# FTDI.net
KiCad netlist of a schematic drawn in Altium Designer
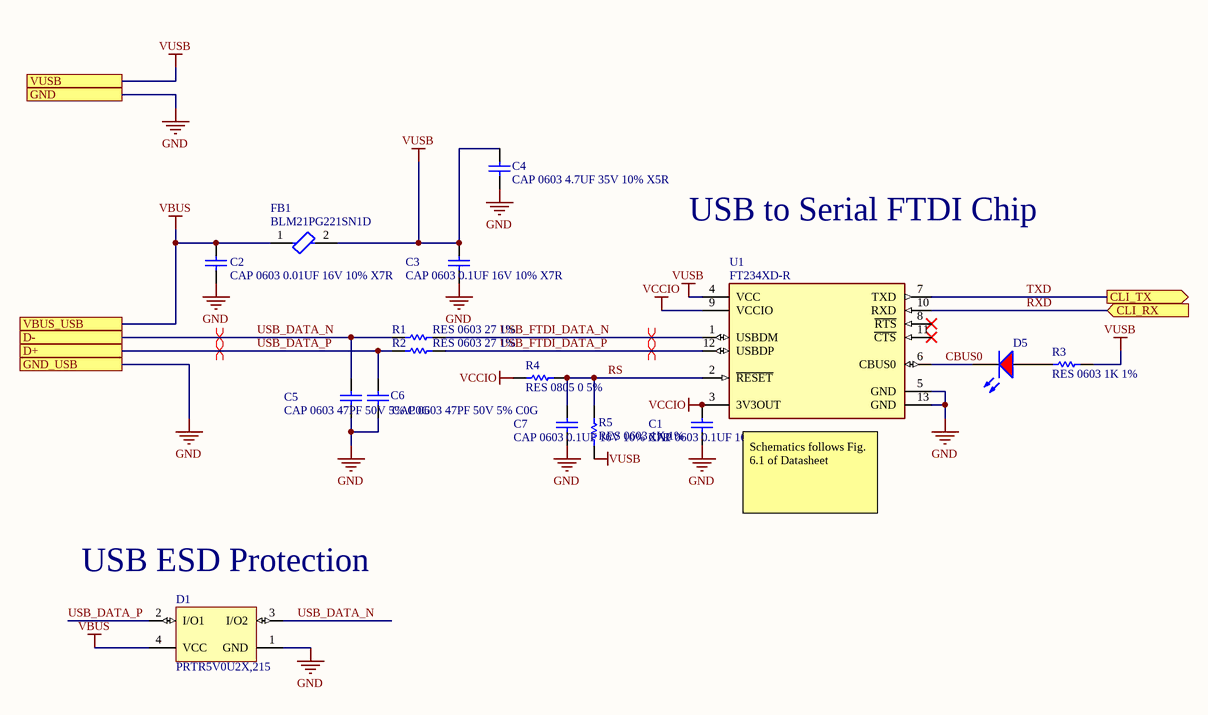
[diagram p0: FTDI.SchDoc]

(export (version "E")
  (design (tool "Eeschema 10.0.6"))
  (components
    (comp (ref "C1")
      (value "CAP 0603 0.1UF 16V 10% X7R")
      (footprint "0603_CAP")
      (description "Capacitor Surface Mount 0603 Footprint 0.1UF 16V 10% Tolerance Ceramic X7R")
      (fields (field (name "VOLTAGE") "16V") (field (name "MANUFACTURER") "Various"))
      (libsource (lib "University of Pennsylvania (ESE Labs)") (part "cap"))
    )
    (comp (ref "C2")
      (value "CAP 0603 0.01UF 16V 10% X7R")
      (footprint "0603_CAP")
      (description "Capacitor Surface Mount 0603 Footprint 0.01UF 16V 10% Tolerance Ceramic X7R")
      (fields (field (name "MANUFACTURER") "Various") (field (name "VOLTAGE") "16V"))
      (libsource (lib "University of Pennsylvania (ESE Labs)") (part "cap"))
    )
    (comp (ref "C3")
      (value "CAP 0603 0.1UF 16V 10% X7R")
      (footprint "0603_CAP")
      (description "Capacitor Surface Mount 0603 Footprint 0.1UF 16V 10% Tolerance Ceramic X7R")
      (fields (field (name "VOLTAGE") "16V") (field (name "MANUFACTURER") "Various"))
      (libsource (lib "University of Pennsylvania (ESE Labs)") (part "cap"))
    )
    (comp (ref "C4")
      (value "CAP 0603 4.7UF 35V 10% X5R")
      (footprint "0603_CAP")
      (description "Capacitor Surface Mount 0603 Footprint 47UF 35V 10% Tolerance Ceramic X5R")
      (fields (field (name "MANUFACTURER") "Various"))
      (libsource (lib "University of Pennsylvania (ESE Labs)") (part "cap"))
    )
    (comp (ref "C5")
      (value "CAP 0603 47PF 50V 5% C0G")
      (footprint "0603_CAP")
      (description "Capacitor Surface Mount 0603 Footprint 47PF 50V 5% Tolerance Ceramic C0G")
      (fields (field (name "MANUFACTURER") "Various") (field (name "VOLTAGE") "50V"))
      (libsource (lib "University of Pennsylvania (ESE Labs)") (part "cap"))
    )
    (comp (ref "C6")
      (value "CAP 0603 47PF 50V 5% C0G")
      (footprint "0603_CAP")
      (description "Capacitor Surface Mount 0603 Footprint 47PF 50V 5% Tolerance Ceramic C0G")
      (fields (field (name "MANUFACTURER") "Various") (field (name "VOLTAGE") "50V"))
      (libsource (lib "University of Pennsylvania (ESE Labs)") (part "cap"))
    )
    (comp (ref "C7")
      (value "CAP 0603 0.1UF 16V 10% X7R")
      (footprint "0603_CAP")
      (description "Capacitor Surface Mount 0603 Footprint 0.1UF 16V 10% Tolerance Ceramic X7R")
      (fields (field (name "VOLTAGE") "16V") (field (name "MANUFACTURER") "Various"))
      (libsource (lib "University of Pennsylvania (ESE Labs)") (part "cap"))
    )
    (comp (ref "D1")
      (value "PRTR5V0U2X,215")
      (footprint "NXP-SOT143B-4_V")
      (fields (field (name "MANUFACTURER") "NXP Semiconductors"))
      (libsource (lib "Altium Content Vault") (part "NXP-PRTR5V0U2X,215-4"))
    )
    (comp (ref "D5")
      (value "LSM0805412V")
      (footprint "LED_0805_RED")
      (description "Single Color LED, RED, 0805")
      (libsource (lib "University of Pennsylvania (ESE Labs)") (part "LED-RED-AK-2"))
    )
    (comp (ref "FB1")
      (value "BLM21PG221SN1D")
      (footprint "FP-BLM21-0_2-t0_85-e0_5-IPC_B")
      (description "Chip Ferrite Bead, 0805, 220Ω @ 100MHz, 0.045Ω, 25%, 2A")
      (fields (field (name "TOLERANCE") "25%"))
      (libsource (lib "Altium Content Vault") (part "5f30dd21d616792df468990f7003faa"))
    )
    (comp (ref "R1")
      (value "RES 0603 27 1%")
      (footprint "0603_RES")
      (description "Resistor Surface Mount, 27 Ohms, 0603 Footprint, 1% Tolerance 0.1W")
      (fields (field (name "TOLERANCE") "1%") (field (name "MANUFACTURER") "Various"))
      (libsource (lib "University of Pennsylvania (ESE Labs)") (part "res"))
    )
    (comp (ref "R2")
      (value "RES 0603 27 1%")
      (footprint "0603_RES")
      (description "Resistor Surface Mount, 27 Ohms, 0603 Footprint, 1% Tolerance 0.1W")
      (fields (field (name "TOLERANCE") "1%") (field (name "MANUFACTURER") "Various"))
      (libsource (lib "University of Pennsylvania (ESE Labs)") (part "res"))
    )
    (comp (ref "R3")
      (value "RES 0603 1K 1%")
      (footprint "0603_RES")
      (description "Resistor Surface Mount, 1K Ohms, 0603 Footprint, 1% Tolerance 0.1W")
      (fields (field (name "MANUFACTURER") "Various") (field (name "TOLERANCE") "1%"))
      (libsource (lib "University of Pennsylvania (ESE Labs)") (part "res"))
    )
    (comp (ref "R4")
      (value "RES 0805 0 5%")
      (footprint "0805_RES")
      (description "Resistor Surface Mount, 0 Ohms, 0805 Footprint, 5% Tolerance 0.125W")
      (fields (field (name "MANUFACTURER") "Various") (field (name "TOLERANCE") "5%"))
      (libsource (lib "University of Pennsylvania (ESE Labs)") (part "res"))
    )
    (comp (ref "R5")
      (value "RES 0603 1K 1%")
      (footprint "0603_RES")
      (description "Resistor Surface Mount, 1K Ohms, 0603 Footprint, 1% Tolerance 0.1W")
      (fields (field (name "MANUFACTURER") "Various") (field (name "TOLERANCE") "1%"))
      (libsource (lib "University of Pennsylvania (ESE Labs)") (part "res"))
    )
    (comp (ref "U1")
      (value "FT234XD-R")
      (footprint "FP-DFN-12-IPC_B")
      (description "IC USB SERIAL BASIC UART 12DFN")
      (libsource (lib "Altium Content Vault") (part "4bef3367ed9f9051bcb84ab46edda1c"))
    )
  )
  (nets
    (net (code "1") (name "/CBUS0") (class "Default")
      (node (ref "D5") (pin "K") (pinfunction "K_K") (pintype "passive"))
      (node (ref "U1") (pin "6") (pinfunction "CBUS0_6") (pintype "bidirectional"))
    )
    (net (code "2") (name "/RS") (class "Default")
      (node (ref "C7") (pin "2") (pinfunction "2_2") (pintype "passive"))
      (node (ref "R4") (pin "2") (pinfunction "2_2") (pintype "passive"))
      (node (ref "R5") (pin "2") (pinfunction "2_2") (pintype "passive"))
      (node (ref "U1") (pin "2") (pinfunction "~{RESET}_2") (pintype "input"))
    )
    (net (code "3") (name "/RXD") (class "Default")
      (node (ref "U1") (pin "10") (pinfunction "RXD_10") (pintype "input"))
    )
    (net (code "4") (name "/TXD") (class "Default")
      (node (ref "U1") (pin "7") (pinfunction "TXD_7") (pintype "output"))
    )
    (net (code "5") (name "/USB_DATA_N") (class "Default")
      (node (ref "C5") (pin "2") (pinfunction "2_2") (pintype "passive"))
      (node (ref "D1") (pin "3") (pinfunction "I/O2_3") (pintype "bidirectional"))
      (node (ref "R1") (pin "1") (pinfunction "1_1") (pintype "passive"))
    )
    (net (code "6") (name "/USB_DATA_P") (class "Default")
      (node (ref "C6") (pin "2") (pinfunction "2_2") (pintype "passive"))
      (node (ref "D1") (pin "2") (pinfunction "I/O1_2") (pintype "bidirectional"))
      (node (ref "R2") (pin "1") (pinfunction "1_1") (pintype "passive"))
    )
    (net (code "7") (name "/USB_FTDI_DATA_N") (class "Default")
      (node (ref "R1") (pin "2") (pinfunction "2_2") (pintype "passive"))
      (node (ref "U1") (pin "1") (pinfunction "USBDM_1") (pintype "bidirectional"))
    )
    (net (code "8") (name "/USB_FTDI_DATA_P") (class "Default")
      (node (ref "R2") (pin "2") (pinfunction "2_2") (pintype "passive"))
      (node (ref "U1") (pin "12") (pinfunction "USBDP_12") (pintype "bidirectional"))
    )
    (net (code "9") (name "GND") (class "Default")
      (node (ref "C1") (pin "1") (pinfunction "1_1") (pintype "passive"))
      (node (ref "C2") (pin "1") (pinfunction "1_1") (pintype "passive"))
      (node (ref "C3") (pin "1") (pinfunction "1_1") (pintype "passive"))
      (node (ref "C4") (pin "1") (pinfunction "1_1") (pintype "passive"))
      (node (ref "C5") (pin "1") (pinfunction "1_1") (pintype "passive"))
      (node (ref "C6") (pin "1") (pinfunction "1_1") (pintype "passive"))
      (node (ref "C7") (pin "1") (pinfunction "1_1") (pintype "passive"))
      (node (ref "D1") (pin "1") (pinfunction "GND_1") (pintype "power_in"))
      (node (ref "U1") (pin "13") (pinfunction "GND_13") (pintype "power_in"))
      (node (ref "U1") (pin "5") (pinfunction "GND_5") (pintype "power_in"))
    )
    (net (code "10") (name "Net-(D5-PadA)") (class "Default")
      (node (ref "D5") (pin "A") (pinfunction "A_A") (pintype "passive"))
      (node (ref "R3") (pin "2") (pinfunction "2_2") (pintype "passive"))
    )
    (net (code "11") (name "VBUS") (class "Default")
      (node (ref "C2") (pin "2") (pinfunction "2_2") (pintype "passive"))
      (node (ref "D1") (pin "4") (pinfunction "VCC_4") (pintype "power_in"))
      (node (ref "FB1") (pin "1") (pinfunction "1_1") (pintype "passive"))
    )
    (net (code "12") (name "VCCIO") (class "Default")
      (node (ref "C1") (pin "2") (pinfunction "2_2") (pintype "passive"))
      (node (ref "R4") (pin "1") (pinfunction "1_1") (pintype "passive"))
      (node (ref "U1") (pin "3") (pinfunction "3V3OUT_3") (pintype "power_in"))
      (node (ref "U1") (pin "9") (pinfunction "VCCIO_9") (pintype "power_in"))
    )
    (net (code "13") (name "VUSB") (class "Default")
      (node (ref "C3") (pin "2") (pinfunction "2_2") (pintype "passive"))
      (node (ref "C4") (pin "2") (pinfunction "2_2") (pintype "passive"))
      (node (ref "FB1") (pin "2") (pinfunction "2_2") (pintype "passive"))
      (node (ref "R3") (pin "1") (pinfunction "1_1") (pintype "passive"))
      (node (ref "R5") (pin "1") (pinfunction "1_1") (pintype "passive"))
      (node (ref "U1") (pin "4") (pinfunction "VCC_4") (pintype "power_in"))
    )
    (net (code "14") (name "unconnected-(U1-~{CTS}-Pad11)") (class "Default")
      (node (ref "U1") (pin "11") (pinfunction "~{CTS}_11") (pintype "input+no_connect"))
    )
    (net (code "15") (name "unconnected-(U1-~{RTS}-Pad8)") (class "Default")
      (node (ref "U1") (pin "8") (pinfunction "~{RTS}_8") (pintype "input+no_connect"))
    )
  )
)
